# TeamH_PDB_SCH.net
KiCad netlist of a schematic drawn in EAGLE
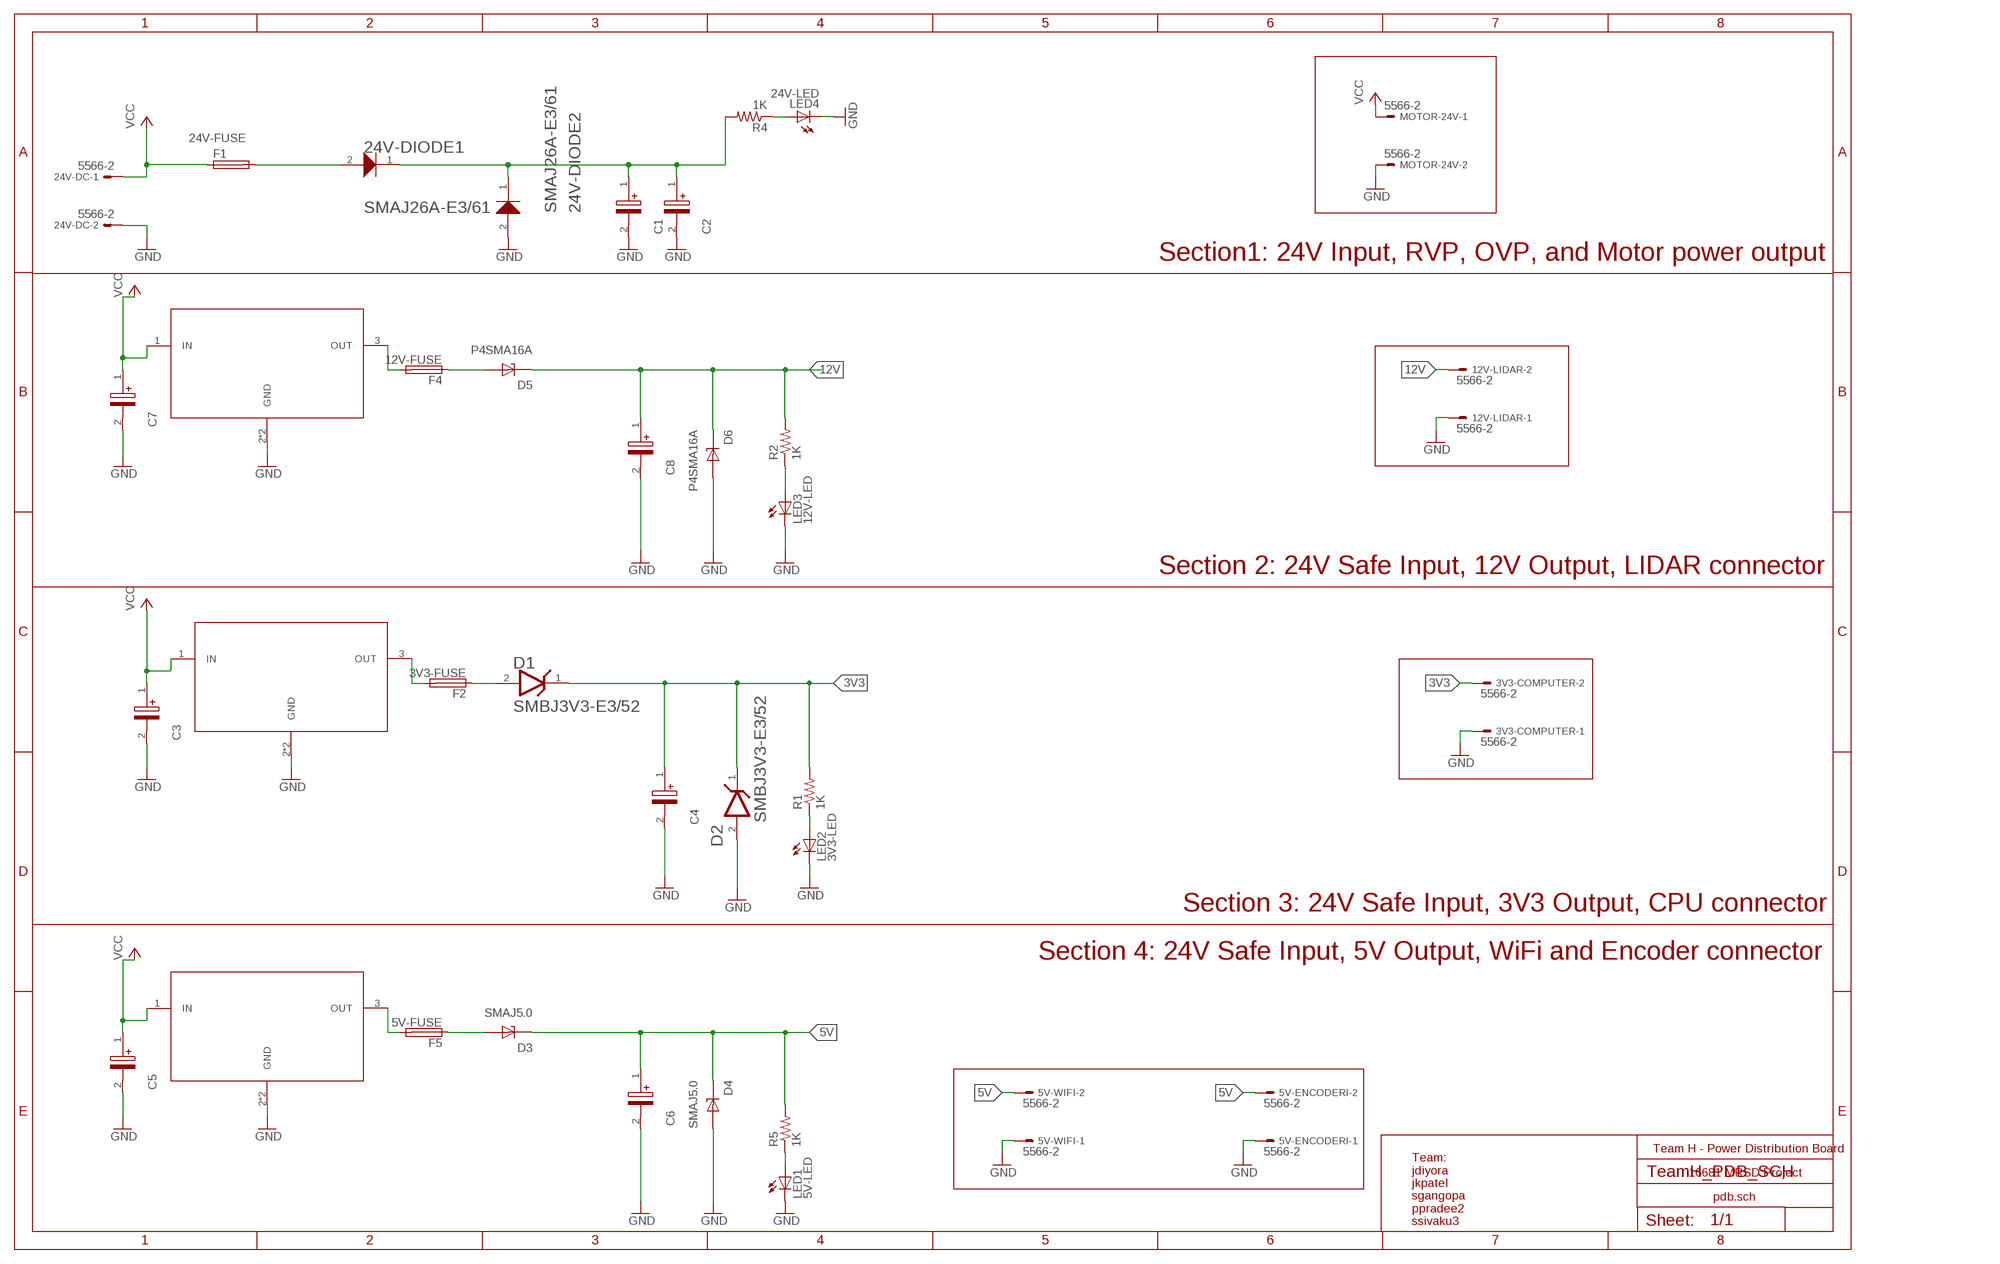
[diagram p0: schematic, sheet 1]

(export (version "E")
  (design (tool "Eeschema 10.0.6"))
  (components
    (comp (ref "3V3-COMPUTER")
      (value "5566-2")
      (footprint "eagle-import:5566-2")
      (fields (field (name "MF") "MOLEX"))
      (libsource (lib "eagle-import") (part "5566-2"))
    )
    (comp (ref "5V-ENCODERI")
      (value "5566-2")
      (footprint "eagle-import:5566-2")
      (fields (field (name "MF") "MOLEX"))
      (libsource (lib "eagle-import") (part "5566-2"))
    )
    (comp (ref "5V-WIFI")
      (value "5566-2")
      (footprint "eagle-import:5566-2")
      (fields (field (name "MF") "MOLEX"))
      (libsource (lib "eagle-import") (part "5566-2"))
    )
    (comp (ref "12V-LIDAR")
      (value "5566-2")
      (footprint "eagle-import:5566-2")
      (fields (field (name "MF") "MOLEX"))
      (libsource (lib "eagle-import") (part "5566-2"))
    )
    (comp (ref "24V-DC")
      (value "5566-2")
      (footprint "eagle-import:5566-2")
      (fields (field (name "MF") "MOLEX"))
      (libsource (lib "eagle-import") (part "5566-2"))
    )
    (comp (ref "24V-DIODE1")
      (value "24V TVS")
      (footprint "eagle-import:VISHAY_SEMICONDUCTOR_SMAJ26A-E3-61_2")
      (fields (field (name "MF") "Vishay Semiconductor") (field (name "MPN") "SMAJ26A-E3/61"))
      (libsource (lib "eagle-import") (part "VISHAY_SEMICONDUCTOR_SMAJ26A-E3-61VISHAY_SEMICONDUCTOR_SMAJ26A-E3-61_0_2"))
    )
    (comp (ref "24V-DIODE2")
      (value "24V TVS")
      (footprint "eagle-import:VISHAY_SEMICONDUCTOR_SMAJ26A-E3-61_2")
      (fields (field (name "MF") "Vishay Semiconductor") (field (name "MPN") "SMAJ26A-E3/61"))
      (libsource (lib "eagle-import") (part "VISHAY_SEMICONDUCTOR_SMAJ26A-E3-61VISHAY_SEMICONDUCTOR_SMAJ26A-E3-61_0_2"))
    )
    (comp (ref "C1")
      (value "0.1uF")
      (footprint "eagle-import:CAPPM3216X180N")
      (fields
        (field (name "MANUFACTURER_PART_NUMBER") "T489A106K010ATA2K2")
        (field (name "MOUSER_PART_NUMBER") "80-T489A106K10ATA2K2")
      )
      (libsource (lib "eagle-import") (part "T489A106K010ATA2K2"))
    )
    (comp (ref "C2")
      (value "10uF")
      (footprint "eagle-import:CAPPM3216X180N")
      (fields
        (field (name "MANUFACTURER_PART_NUMBER") "T489A106K010ATA2K2")
        (field (name "MOUSER_PART_NUMBER") "80-T489A106K10ATA2K2")
      )
      (libsource (lib "eagle-import") (part "T489A106K010ATA2K2"))
    )
    (comp (ref "C3")
      (value "0.1uF")
      (footprint "eagle-import:CAPPM3216X180N")
      (fields
        (field (name "MANUFACTURER_PART_NUMBER") "T489A106K010ATA2K2")
        (field (name "MOUSER_PART_NUMBER") "80-T489A106K10ATA2K2")
      )
      (libsource (lib "eagle-import") (part "T489A106K010ATA2K2"))
    )
    (comp (ref "C4")
      (value "0.1uF")
      (footprint "eagle-import:CAPPM3216X180N")
      (fields
        (field (name "MANUFACTURER_PART_NUMBER") "T489A106K010ATA2K2")
        (field (name "MOUSER_PART_NUMBER") "80-T489A106K10ATA2K2")
      )
      (libsource (lib "eagle-import") (part "T489A106K010ATA2K2"))
    )
    (comp (ref "C5")
      (value "0.1uF")
      (footprint "eagle-import:CAPPM3216X180N")
      (fields
        (field (name "MANUFACTURER_PART_NUMBER") "T489A106K010ATA2K2")
        (field (name "MOUSER_PART_NUMBER") "80-T489A106K10ATA2K2")
      )
      (libsource (lib "eagle-import") (part "T489A106K010ATA2K2"))
    )
    (comp (ref "C6")
      (value "0.1uF")
      (footprint "eagle-import:CAPPM3216X180N")
      (fields
        (field (name "MANUFACTURER_PART_NUMBER") "T489A106K010ATA2K2")
        (field (name "MOUSER_PART_NUMBER") "80-T489A106K10ATA2K2")
      )
      (libsource (lib "eagle-import") (part "T489A106K010ATA2K2"))
    )
    (comp (ref "C7")
      (value "0.1uF")
      (footprint "eagle-import:CAPPM3216X180N")
      (fields
        (field (name "MANUFACTURER_PART_NUMBER") "T489A106K010ATA2K2")
        (field (name "MOUSER_PART_NUMBER") "80-T489A106K10ATA2K2")
      )
      (libsource (lib "eagle-import") (part "T489A106K010ATA2K2"))
    )
    (comp (ref "C8")
      (value "0.1uF")
      (footprint "eagle-import:CAPPM3216X180N")
      (fields
        (field (name "MANUFACTURER_PART_NUMBER") "T489A106K010ATA2K2")
        (field (name "MOUSER_PART_NUMBER") "80-T489A106K10ATA2K2")
      )
      (libsource (lib "eagle-import") (part "T489A106K010ATA2K2"))
    )
    (comp (ref "D1")
      (value "VISHAY_SMBJ3V3-E3-52VISHAY_SMBJ3V3-E3-52_0_0")
      (footprint "eagle-import:VISHAY_SMBJ3V3-E3-52_0")
      (fields
        (field (name "DIGIKEY_PART_NUMBER") "SMBJ3V3-E3/52GICT-ND")
        (field (name "MF") "Vishay")
        (field (name "MOUSER_PART_NUMBER") "625-SMBJ3V3-E3")
      )
      (libsource (lib "eagle-import") (part "VISHAY_SMBJ3V3-E3-52VISHAY_SMBJ3V3-E3-52_0_0"))
    )
    (comp (ref "D2")
      (value "VISHAY_SMBJ3V3-E3-52VISHAY_SMBJ3V3-E3-52_0_0")
      (footprint "eagle-import:VISHAY_SMBJ3V3-E3-52_0")
      (fields
        (field (name "DIGIKEY_PART_NUMBER") "SMBJ3V3-E3/52GICT-ND")
        (field (name "MF") "Vishay")
        (field (name "MOUSER_PART_NUMBER") "625-SMBJ3V3-E3")
      )
      (libsource (lib "eagle-import") (part "VISHAY_SMBJ3V3-E3-52VISHAY_SMBJ3V3-E3-52_0_0"))
    )
    (comp (ref "D3")
      (value "SMAJ5.0")
      (footprint "eagle-import:DIOM4325X250N")
      (fields (field (name "MF") "Littelfuse"))
      (libsource (lib "eagle-import") (part "SMAJ5.0"))
    )
    (comp (ref "D4")
      (value "SMAJ5.0")
      (footprint "eagle-import:DIOM4325X250N")
      (fields (field (name "MF") "Littelfuse"))
      (libsource (lib "eagle-import") (part "SMAJ5.0"))
    )
    (comp (ref "D5")
      (value "P4SMA16A")
      (footprint "eagle-import:DIOM4325X250N")
      (fields (field (name "MF") "Taiwan Semiconductor"))
      (libsource (lib "eagle-import") (part "P4SMA16A"))
    )
    (comp (ref "D6")
      (value "P4SMA16A")
      (footprint "eagle-import:DIOM4325X250N")
      (fields (field (name "MF") "Taiwan Semiconductor"))
      (libsource (lib "eagle-import") (part "P4SMA16A"))
    )
    (comp (ref "F1")
      (value "24V-FUSE")
      (footprint "eagle-import:TE5")
      (libsource (lib "eagle-import") (part "TE5"))
    )
    (comp (ref "F2")
      (value "3V3-FUSE")
      (footprint "eagle-import:TE5")
      (libsource (lib "eagle-import") (part "TE5"))
    )
    (comp (ref "F4")
      (value "12V-FUSE")
      (footprint "eagle-import:TE5")
      (libsource (lib "eagle-import") (part "TE5"))
    )
    (comp (ref "F5")
      (value "5V-FUSE")
      (footprint "eagle-import:TE5")
      (libsource (lib "eagle-import") (part "TE5"))
    )
    (comp (ref "LED1")
      (value "5V-LED")
      (footprint "eagle-import:CHIPLED_1206")
      (libsource (lib "eagle-import") (part "LEDCHIPLED_1206"))
    )
    (comp (ref "LED2")
      (value "3V3-LED")
      (footprint "eagle-import:CHIPLED_1206")
      (libsource (lib "eagle-import") (part "LEDCHIPLED_1206"))
    )
    (comp (ref "LED3")
      (value "12V-LED")
      (footprint "eagle-import:CHIPLED_1206")
      (libsource (lib "eagle-import") (part "LEDCHIPLED_1206"))
    )
    (comp (ref "LED4")
      (value "24V-LED")
      (footprint "eagle-import:CHIPLED_1206")
      (libsource (lib "eagle-import") (part "LEDCHIPLED_1206"))
    )
    (comp (ref "MIC29300-3V3")
      (value "3v3")
      (footprint "eagle-import:TO263")
      (fields (field (name "MF") "Microchip Technology") (field (name "MP") "MIC29300-12WU"))
      (libsource (lib "eagle-import") (part "MIC29300-12WU"))
    )
    (comp (ref "MIC29300-5V")
      (value "5v")
      (footprint "eagle-import:TO263")
      (fields (field (name "MF") "Microchip Technology") (field (name "MP") "MIC29300-12WU"))
      (libsource (lib "eagle-import") (part "MIC29300-12WU"))
    )
    (comp (ref "MIC29300-12V")
      (value "12v")
      (footprint "eagle-import:TO263")
      (fields (field (name "MF") "Microchip Technology") (field (name "MP") "MIC29300-12WU"))
      (libsource (lib "eagle-import") (part "MIC29300-12WU"))
    )
    (comp (ref "MOTOR-24V")
      (value "5566-2")
      (footprint "eagle-import:5566-2")
      (fields (field (name "MF") "MOLEX"))
      (libsource (lib "eagle-import") (part "5566-2"))
    )
    (comp (ref "R1")
      (value "1K")
      (footprint "eagle-import:R1206")
      (libsource (lib "eagle-import") (part "R-US_R1206"))
    )
    (comp (ref "R2")
      (value "1K")
      (footprint "eagle-import:R1206")
      (libsource (lib "eagle-import") (part "R-US_R1206"))
    )
    (comp (ref "R4")
      (value "1K")
      (footprint "eagle-import:R1206")
      (libsource (lib "eagle-import") (part "R-US_R1206"))
    )
    (comp (ref "R5")
      (value "1K")
      (footprint "eagle-import:R1206")
      (libsource (lib "eagle-import") (part "R-US_R1206"))
    )
  )
  (nets
    (net (code "1") (name "3V3") (class "Default")
      (node (ref "3V3-COMPUTER") (pin "2") (pinfunction "S_2") (pintype "passive"))
      (node (ref "C4") (pin "1") (pinfunction "+_1") (pintype "bidirectional"))
      (node (ref "D1") (pin "1") (pinfunction "CATHODE_1") (pintype "passive"))
      (node (ref "D2") (pin "1") (pinfunction "CATHODE_1") (pintype "passive"))
      (node (ref "R1") (pin "2") (pinfunction "2_2") (pintype "passive"))
    )
    (net (code "2") (name "5V") (class "Default")
      (node (ref "5V-ENCODERI") (pin "2") (pinfunction "S_2") (pintype "passive"))
      (node (ref "5V-WIFI") (pin "2") (pinfunction "S_2") (pintype "passive"))
      (node (ref "C6") (pin "1") (pinfunction "+_1") (pintype "bidirectional"))
      (node (ref "D3") (pin "C") (pinfunction "C_C") (pintype "passive"))
      (node (ref "D4") (pin "C") (pinfunction "C_C") (pintype "passive"))
      (node (ref "R5") (pin "2") (pinfunction "2_2") (pintype "passive"))
    )
    (net (code "3") (name "12V") (class "Default")
      (node (ref "12V-LIDAR") (pin "2") (pinfunction "S_2") (pintype "passive"))
      (node (ref "C8") (pin "1") (pinfunction "+_1") (pintype "bidirectional"))
      (node (ref "D5") (pin "C") (pinfunction "C_C") (pintype "passive"))
      (node (ref "D6") (pin "C") (pinfunction "C_C") (pintype "passive"))
      (node (ref "R2") (pin "2") (pinfunction "2_2") (pintype "passive"))
    )
    (net (code "4") (name "GND") (class "Default")
      (node (ref "12V-LIDAR") (pin "1") (pinfunction "S_1") (pintype "passive"))
      (node (ref "24V-DC") (pin "2") (pinfunction "S_2") (pintype "passive"))
      (node (ref "24V-DIODE2") (pin "2") (pinfunction "A_2") (pintype "passive"))
      (node (ref "3V3-COMPUTER") (pin "1") (pinfunction "S_1") (pintype "passive"))
      (node (ref "5V-ENCODERI") (pin "1") (pinfunction "S_1") (pintype "passive"))
      (node (ref "5V-WIFI") (pin "1") (pinfunction "S_1") (pintype "passive"))
      (node (ref "C1") (pin "2") (pinfunction "-_2") (pintype "bidirectional"))
      (node (ref "C2") (pin "2") (pinfunction "-_2") (pintype "bidirectional"))
      (node (ref "C3") (pin "2") (pinfunction "-_2") (pintype "bidirectional"))
      (node (ref "C4") (pin "2") (pinfunction "-_2") (pintype "bidirectional"))
      (node (ref "C5") (pin "2") (pinfunction "-_2") (pintype "bidirectional"))
      (node (ref "C6") (pin "2") (pinfunction "-_2") (pintype "bidirectional"))
      (node (ref "C7") (pin "2") (pinfunction "-_2") (pintype "bidirectional"))
      (node (ref "C8") (pin "2") (pinfunction "-_2") (pintype "bidirectional"))
      (node (ref "D2") (pin "2") (pinfunction "ANODE_2") (pintype "passive"))
      (node (ref "D4") (pin "A") (pinfunction "A_A") (pintype "passive"))
      (node (ref "D6") (pin "A") (pinfunction "A_A") (pintype "passive"))
      (node (ref "LED1") (pin "C") (pinfunction "C_C") (pintype "passive"))
      (node (ref "LED2") (pin "C") (pinfunction "C_C") (pintype "passive"))
      (node (ref "LED3") (pin "C") (pinfunction "C_C") (pintype "passive"))
      (node (ref "LED4") (pin "C") (pinfunction "C_C") (pintype "passive"))
      (node (ref "MIC29300-12V") (pin "2") (pinfunction "GND_2") (pintype "power_in"))
      (node (ref "MIC29300-12V") (pin "GND@") (pinfunction "GND_GND@") (pintype "power_in"))
      (node (ref "MIC29300-3V3") (pin "2") (pinfunction "GND_2") (pintype "power_in"))
      (node (ref "MIC29300-3V3") (pin "GND@") (pinfunction "GND_GND@") (pintype "power_in"))
      (node (ref "MIC29300-5V") (pin "2") (pinfunction "GND_2") (pintype "power_in"))
      (node (ref "MIC29300-5V") (pin "GND@") (pinfunction "GND_GND@") (pintype "power_in"))
      (node (ref "MOTOR-24V") (pin "2") (pinfunction "S_2") (pintype "passive"))
    )
    (net (code "5") (name "Net-(24V-DIODE1-A)") (class "Default")
      (node (ref "24V-DIODE1") (pin "2") (pinfunction "A_2") (pintype "passive"))
      (node (ref "F1") (pin "2") (pinfunction "2_2") (pintype "passive"))
    )
    (net (code "6") (name "Net-(24V-DIODE1-K)") (class "Default")
      (node (ref "24V-DIODE1") (pin "1") (pinfunction "K_1") (pintype "passive"))
      (node (ref "24V-DIODE2") (pin "1") (pinfunction "K_1") (pintype "passive"))
      (node (ref "C1") (pin "1") (pinfunction "+_1") (pintype "bidirectional"))
      (node (ref "C2") (pin "1") (pinfunction "+_1") (pintype "bidirectional"))
      (node (ref "R4") (pin "2") (pinfunction "2_2") (pintype "passive"))
    )
    (net (code "7") (name "Net-(D1-ANODE)") (class "Default")
      (node (ref "D1") (pin "2") (pinfunction "ANODE_2") (pintype "passive"))
      (node (ref "F2") (pin "1") (pinfunction "1_1") (pintype "passive"))
    )
    (net (code "8") (name "Net-(D3-PadA)") (class "Default")
      (node (ref "D3") (pin "A") (pinfunction "A_A") (pintype "passive"))
      (node (ref "F5") (pin "1") (pinfunction "1_1") (pintype "passive"))
    )
    (net (code "9") (name "Net-(D5-PadA)") (class "Default")
      (node (ref "D5") (pin "A") (pinfunction "A_A") (pintype "passive"))
      (node (ref "F4") (pin "1") (pinfunction "1_1") (pintype "passive"))
    )
    (net (code "10") (name "Net-(LED1-PadA)") (class "Default")
      (node (ref "LED1") (pin "A") (pinfunction "A_A") (pintype "passive"))
      (node (ref "R5") (pin "1") (pinfunction "1_1") (pintype "passive"))
    )
    (net (code "11") (name "Net-(LED2-PadA)") (class "Default")
      (node (ref "LED2") (pin "A") (pinfunction "A_A") (pintype "passive"))
      (node (ref "R1") (pin "1") (pinfunction "1_1") (pintype "passive"))
    )
    (net (code "12") (name "Net-(LED3-PadA)") (class "Default")
      (node (ref "LED3") (pin "A") (pinfunction "A_A") (pintype "passive"))
      (node (ref "R2") (pin "1") (pinfunction "1_1") (pintype "passive"))
    )
    (net (code "13") (name "Net-(LED4-PadA)") (class "Default")
      (node (ref "LED4") (pin "A") (pinfunction "A_A") (pintype "passive"))
      (node (ref "R4") (pin "1") (pinfunction "1_1") (pintype "passive"))
    )
    (net (code "14") (name "Net-(MIC29300-3V3-OUT)") (class "Default")
      (node (ref "F2") (pin "2") (pinfunction "2_2") (pintype "passive"))
      (node (ref "MIC29300-3V3") (pin "3") (pinfunction "OUT_3") (pintype "output"))
    )
    (net (code "15") (name "Net-(MIC29300-5V-OUT)") (class "Default")
      (node (ref "F5") (pin "2") (pinfunction "2_2") (pintype "passive"))
      (node (ref "MIC29300-5V") (pin "3") (pinfunction "OUT_3") (pintype "output"))
    )
    (net (code "16") (name "Net-(MIC29300-12V-OUT)") (class "Default")
      (node (ref "F4") (pin "2") (pinfunction "2_2") (pintype "passive"))
      (node (ref "MIC29300-12V") (pin "3") (pinfunction "OUT_3") (pintype "output"))
    )
    (net (code "17") (name "VCC") (class "Default")
      (node (ref "24V-DC") (pin "1") (pinfunction "S_1") (pintype "passive"))
      (node (ref "C3") (pin "1") (pinfunction "+_1") (pintype "bidirectional"))
      (node (ref "C5") (pin "1") (pinfunction "+_1") (pintype "bidirectional"))
      (node (ref "C7") (pin "1") (pinfunction "+_1") (pintype "bidirectional"))
      (node (ref "F1") (pin "1") (pinfunction "1_1") (pintype "passive"))
      (node (ref "MIC29300-12V") (pin "1") (pinfunction "IN_1") (pintype "input"))
      (node (ref "MIC29300-3V3") (pin "1") (pinfunction "IN_1") (pintype "input"))
      (node (ref "MIC29300-5V") (pin "1") (pinfunction "IN_1") (pintype "input"))
      (node (ref "MOTOR-24V") (pin "1") (pinfunction "S_1") (pintype "passive"))
    )
  )
)
